# SDM30.net
KiCad netlist of a schematic drawn in Altium Designer
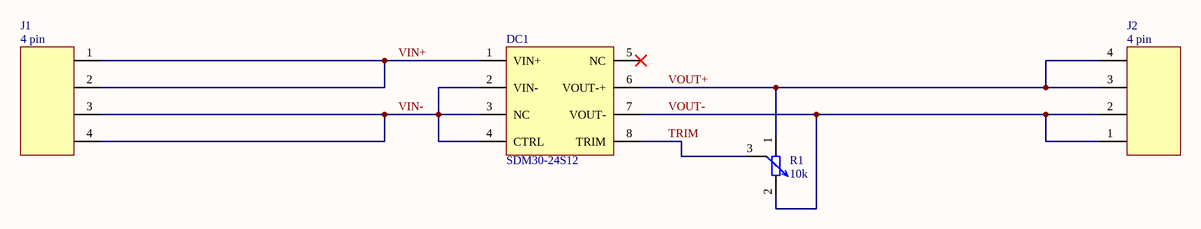
[diagram p0: SDM30.SchDoc]

(export (version "E")
  (design (tool "Eeschema 10.0.6"))
  (components
    (comp (ref "DC1")
      (value "SDM30-24S12")
      (footprint "SDM30-24S12")
      (description "Isolated DC/DC Converters - Through Hole 30W 24Vin 12Vout 2.5A")
      (fields (field (name "MANUFACTURER") "Mean Well"))
      (libsource (lib "Radolovic_SCH_Library") (part "SDM30-24S12"))
    )
    (comp (ref "J1")
      (value "4 pin")
      (footprint "4 pin terminal 5 mm")
      (libsource (lib "") (part "TERMINAL_BLOCK_5mm_4pin_1"))
    )
    (comp (ref "J2")
      (value "4 pin")
      (footprint "4 pin terminal 5 mm")
      (libsource (lib "Radolovic_SCH_Library") (part "TERMINAL_BLOCK_5mm_4pin"))
    )
    (comp (ref "R1")
      (value "10k")
      (footprint "3 pin header")
      (libsource (lib "Radolovic_SCH_Library") (part "RES_POT_THT_generic"))
    )
  )
  (nets
    (net (code "1") (name "/TRIM") (class "Default")
      (node (ref "DC1") (pin "8") (pinfunction "TRIM_8") (pintype "passive"))
      (node (ref "R1") (pin "3") (pintype "passive"))
    )
    (net (code "2") (name "/VIN+") (class "Default")
      (node (ref "DC1") (pin "1") (pinfunction "VIN+_1") (pintype "passive"))
      (node (ref "J1") (pin "1") (pintype "passive"))
      (node (ref "J1") (pin "2") (pintype "passive"))
    )
    (net (code "3") (name "/VIN-") (class "Default")
      (node (ref "DC1") (pin "2") (pinfunction "VIN-_2") (pintype "passive"))
      (node (ref "DC1") (pin "3") (pinfunction "NC_3") (pintype "passive"))
      (node (ref "DC1") (pin "4") (pinfunction "CTRL_4") (pintype "passive"))
      (node (ref "J1") (pin "3") (pintype "passive"))
      (node (ref "J1") (pin "4") (pintype "passive"))
    )
    (net (code "4") (name "/VOUT+") (class "Default")
      (node (ref "DC1") (pin "6") (pinfunction "VOUT-+_6") (pintype "passive"))
      (node (ref "J2") (pin "3") (pintype "passive"))
      (node (ref "J2") (pin "4") (pintype "passive"))
      (node (ref "R1") (pin "1") (pintype "passive"))
    )
    (net (code "5") (name "/VOUT-") (class "Default")
      (node (ref "DC1") (pin "7") (pinfunction "VOUT-_7") (pintype "passive"))
      (node (ref "J2") (pin "1") (pintype "passive"))
      (node (ref "J2") (pin "2") (pintype "passive"))
      (node (ref "R1") (pin "2") (pintype "passive"))
    )
    (net (code "6") (name "unconnected-(DC1-NC-Pad5)") (class "Default")
      (node (ref "DC1") (pin "5") (pinfunction "NC_5") (pintype "passive+no_connect"))
    )
  )
)
